# 12V_Converter.net
KiCad netlist of a schematic drawn in Altium Designer
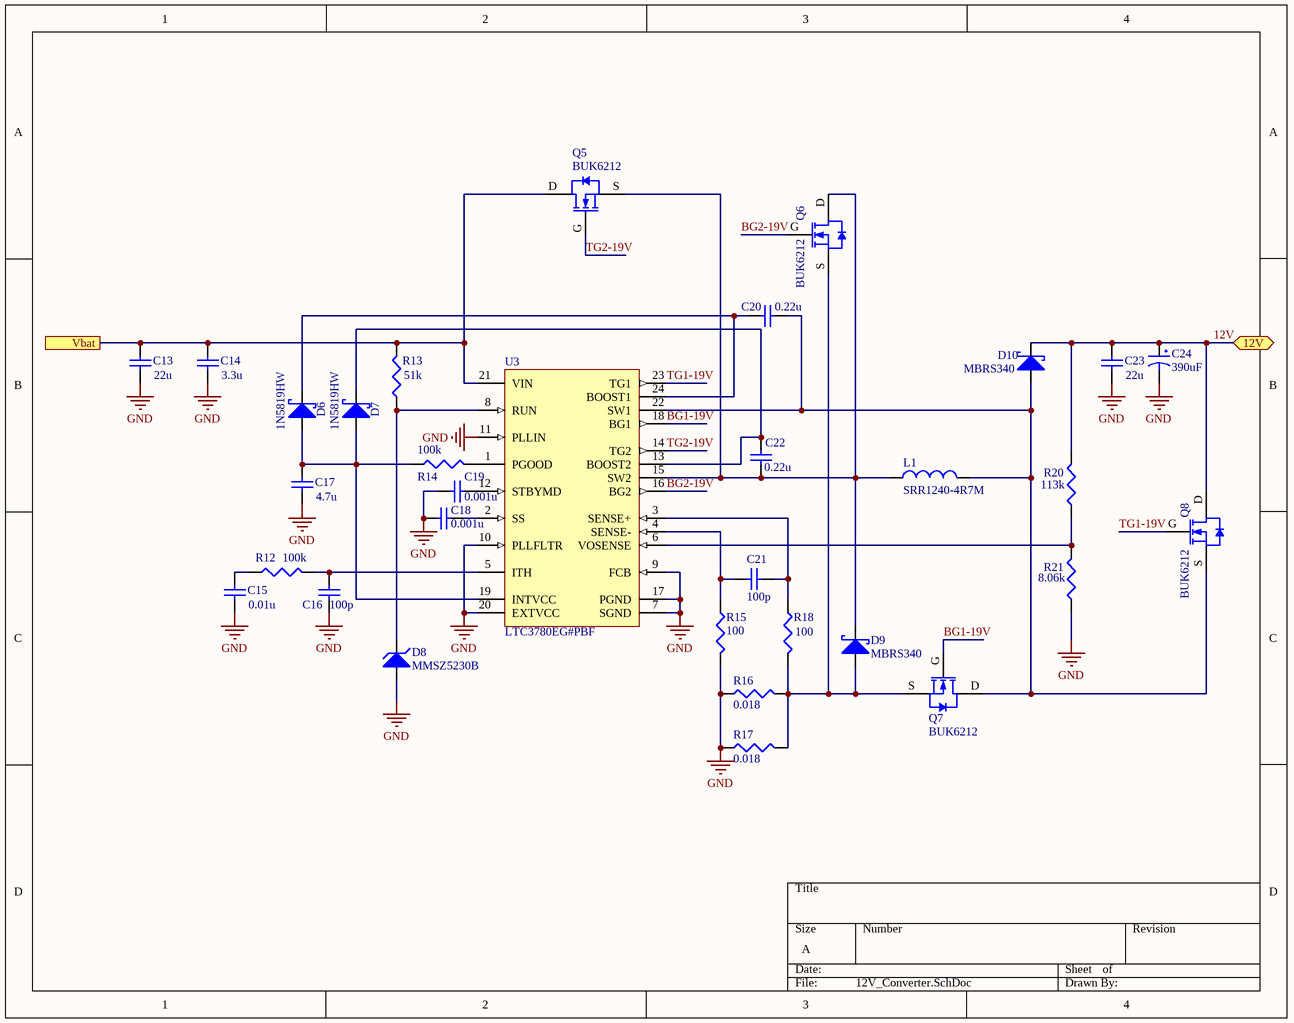
[diagram p0: 12V_Converter.SchDoc]

(export (version "E")
  (design (tool "Eeschema 10.0.6"))
  (components
    (comp (ref "C13")
      (value "22u")
      (footprint "C1206")
      (description "Capacitor (Semiconductor SIM Model)")
      (fields (field (name "Comment") "Cap Semi") (field (name "PUBLISHER") "Altium Limited"))
      (libsource (lib "Miscellaneous Devices") (part "Cap Semi"))
    )
    (comp (ref "C14")
      (value "3.3u")
      (footprint "C1206")
      (description "Capacitor (Semiconductor SIM Model)")
      (fields (field (name "Comment") "Cap Semi") (field (name "PUBLISHER") "Altium Limited"))
      (libsource (lib "Miscellaneous Devices") (part "Cap Semi"))
    )
    (comp (ref "C15")
      (value "0.01u")
      (footprint "C1206")
      (description "Capacitor (Semiconductor SIM Model)")
      (fields (field (name "Comment") "Cap Semi") (field (name "PUBLISHER") "Altium Limited"))
      (libsource (lib "Miscellaneous Devices") (part "Cap Semi"))
    )
    (comp (ref "C16")
      (value "100p")
      (footprint "C1206")
      (description "Capacitor (Semiconductor SIM Model)")
      (fields (field (name "Comment") "Cap Semi") (field (name "PUBLISHER") "Altium Limited"))
      (libsource (lib "Miscellaneous Devices") (part "Cap Semi"))
    )
    (comp (ref "C17")
      (value "4.7u")
      (footprint "C1206")
      (description "Capacitor (Semiconductor SIM Model)")
      (fields (field (name "Comment") "Cap Semi") (field (name "PUBLISHER") "Altium Limited"))
      (libsource (lib "Miscellaneous Devices") (part "Cap Semi"))
    )
    (comp (ref "C18")
      (value "0.001u")
      (footprint "C1206")
      (description "Capacitor (Semiconductor SIM Model)")
      (fields (field (name "Comment") "Cap Semi") (field (name "PUBLISHER") "Altium Limited"))
      (libsource (lib "Miscellaneous Devices") (part "Cap Semi"))
    )
    (comp (ref "C19")
      (value "0.001u")
      (footprint "C1206")
      (description "Capacitor (Semiconductor SIM Model)")
      (fields (field (name "Comment") "Cap Semi") (field (name "PUBLISHER") "Altium Limited"))
      (libsource (lib "Miscellaneous Devices") (part "Cap Semi"))
    )
    (comp (ref "C20")
      (value "0.22u")
      (footprint "C1206")
      (description "Capacitor (Semiconductor SIM Model)")
      (fields (field (name "Comment") "Cap Semi") (field (name "PUBLISHER") "Altium Limited"))
      (libsource (lib "Miscellaneous Devices") (part "Cap Semi"))
    )
    (comp (ref "C21")
      (value "100p")
      (footprint "C1206")
      (description "Capacitor (Semiconductor SIM Model)")
      (fields (field (name "Comment") "Cap Semi") (field (name "PUBLISHER") "Altium Limited"))
      (libsource (lib "Miscellaneous Devices") (part "Cap Semi"))
    )
    (comp (ref "C22")
      (value "0.22u")
      (footprint "C1206")
      (description "Capacitor (Semiconductor SIM Model)")
      (fields (field (name "Comment") "Cap Semi") (field (name "PUBLISHER") "Altium Limited"))
      (libsource (lib "Miscellaneous Devices") (part "Cap Semi"))
    )
    (comp (ref "C23")
      (value "22u")
      (footprint "C1206")
      (description "Capacitor (Semiconductor SIM Model)")
      (fields (field (name "Comment") "Cap Semi") (field (name "PUBLISHER") "Altium Limited"))
      (libsource (lib "Miscellaneous Devices") (part "Cap Semi"))
    )
    (comp (ref "C24")
      (value "390uF")
      (footprint "PCVxxxxxMCLxGS")
      (description "CAP ALUM POLY 390UF 20% 25V SMD")
      (libsource (lib "Power_Embedded_Board_Library") (part "PCV1E391MCL2GS"))
    )
    (comp (ref "D6")
      (value "1N5819HW")
      (footprint "1N58xx")
      (description "1A Schottky Barrier Rectifier Diode")
      (libsource (lib "Power_Embedded_Board_Library") (part "1N58xx"))
    )
    (comp (ref "D7")
      (value "1N5819HW")
      (footprint "1N58xx")
      (description "1A Schottky Barrier Rectifier Diode")
      (libsource (lib "Power_Embedded_Board_Library") (part "1N58xx"))
    )
    (comp (ref "D8")
      (value "MMSZ5230B")
      (footprint "ONSC-SOD-123-2-425-04_V")
      (description "Zener Voltage Regulator, 500 mW, 2-Pin SOD-123, Pb-Free, Tape and Reel")
      (fields (field (name "MANUFACTURER") "On Semiconductor") (field (name "PARTNUMBER") "MMSZ5230BT1G"))
      (libsource (lib "Power_Embedded_Board_Library") (part "MMSZ5230BT1G"))
    )
    (comp (ref "D9")
      (value "MBRS340")
      (footprint "MBRS340")
      (description "Schottky Rectifier")
      (libsource (lib "Power_Embedded_Board_Library") (part "MBRS340"))
    )
    (comp (ref "D10")
      (value "MBRS340")
      (footprint "MBRS340")
      (description "Schottky Rectifier")
      (libsource (lib "Power_Embedded_Board_Library") (part "MBRS340"))
    )
    (comp (ref "L1")
      (value "SRR1240-4R7M")
      (footprint "SRR1240")
      (description "FIXED IND 4.7UH 6A 18 MOHM SMD")
      (libsource (lib "Power_Embedded_Board_Library") (part "SRR1240"))
    )
    (comp (ref "Q5")
      (value "BUK6212")
      (footprint "NXP-SOT428_M")
      (description "N-Channel TrenchMOS Intermediate Level FET, 40 V, 50 A, 3-Pin SOT428, Tape and Reel")
      (fields
        (field (name "MANUFACTURER") "NXP Semiconductors")
        (field (name "PARTNUMBER") "BUK6212-40C,118")
      )
      (libsource (lib "Power_Embedded_Board_Library") (part "BUK6212"))
    )
    (comp (ref "Q6")
      (value "BUK6212")
      (footprint "NXP-SOT428_M")
      (description "N-Channel TrenchMOS Intermediate Level FET, 40 V, 50 A, 3-Pin SOT428, Tape and Reel")
      (fields
        (field (name "MANUFACTURER") "NXP Semiconductors")
        (field (name "PARTNUMBER") "BUK6212-40C,118")
      )
      (libsource (lib "Power_Embedded_Board_Library") (part "BUK6212"))
    )
    (comp (ref "Q7")
      (value "BUK6212")
      (footprint "NXP-SOT428_M")
      (description "N-Channel TrenchMOS Intermediate Level FET, 40 V, 50 A, 3-Pin SOT428, Tape and Reel")
      (fields
        (field (name "MANUFACTURER") "NXP Semiconductors")
        (field (name "PARTNUMBER") "BUK6212-40C,118")
      )
      (libsource (lib "Power_Embedded_Board_Library") (part "BUK6212"))
    )
    (comp (ref "Q8")
      (value "BUK6212")
      (footprint "NXP-SOT428_M")
      (description "N-Channel TrenchMOS Intermediate Level FET, 40 V, 50 A, 3-Pin SOT428, Tape and Reel")
      (fields
        (field (name "MANUFACTURER") "NXP Semiconductors")
        (field (name "PARTNUMBER") "BUK6212-40C,118")
      )
      (libsource (lib "Power_Embedded_Board_Library") (part "BUK6212"))
    )
    (comp (ref "R12")
      (value "100k")
      (footprint "J1-0603")
      (description "Resistor")
      (fields (field (name "Comment") "Res3") (field (name "PUBLISHER") "Altium Limited"))
      (libsource (lib "Miscellaneous Devices") (part "Res3"))
    )
    (comp (ref "R13")
      (value "51k")
      (footprint "J1-0603")
      (description "Resistor")
      (fields (field (name "Comment") "Res3") (field (name "PUBLISHER") "Altium Limited"))
      (libsource (lib "Miscellaneous Devices") (part "Res3"))
    )
    (comp (ref "R14")
      (value "100k")
      (footprint "J1-0603")
      (description "Resistor")
      (fields (field (name "Comment") "Res3") (field (name "PUBLISHER") "Altium Limited"))
      (libsource (lib "Miscellaneous Devices") (part "Res3"))
    )
    (comp (ref "R15")
      (value "100")
      (footprint "J1-0603")
      (description "Resistor")
      (fields (field (name "Comment") "Res3") (field (name "PUBLISHER") "Altium Limited"))
      (libsource (lib "Miscellaneous Devices") (part "Res3"))
    )
    (comp (ref "R16")
      (value "0.018")
      (footprint "R1206")
      (description "Resistor")
      (fields (field (name "Comment") "Res3") (field (name "PUBLISHER") "Altium Limited"))
      (libsource (lib "Miscellaneous Devices") (part "Res3"))
    )
    (comp (ref "R17")
      (value "0.018")
      (footprint "R1206")
      (description "Resistor")
      (fields (field (name "Comment") "Res3") (field (name "PUBLISHER") "Altium Limited"))
      (libsource (lib "Miscellaneous Devices") (part "Res3"))
    )
    (comp (ref "R18")
      (value "100")
      (footprint "J1-0603")
      (description "Resistor")
      (fields (field (name "Comment") "Res3") (field (name "PUBLISHER") "Altium Limited"))
      (libsource (lib "Miscellaneous Devices") (part "Res3"))
    )
    (comp (ref "R20")
      (value "113k")
      (footprint "J1-0603")
      (description "Resistor")
      (fields (field (name "Comment") "Res3") (field (name "PUBLISHER") "Altium Limited"))
      (libsource (lib "Miscellaneous Devices") (part "Res3"))
    )
    (comp (ref "R21")
      (value "8.06k")
      (footprint "J1-0603")
      (description "Resistor")
      (fields (field (name "Comment") "Res3") (field (name "PUBLISHER") "Altium Limited"))
      (libsource (lib "Miscellaneous Devices") (part "Res3"))
    )
    (comp (ref "U3")
      (value "LTC3780EG#PBF")
      (footprint "LT-G-24_L")
      (fields (field (name "MANUFACTURER") "Linear Technology"))
      (libsource (lib "Power_Embedded_Board_Library") (part "LTC3780EG#PBF"))
    )
  )
  (nets
    (net (code "1") (name "/12V") (class "Default")
      (node (ref "C23") (pin "2") (pinfunction "2_2") (pintype "passive"))
      (node (ref "C24") (pin "1") (pinfunction "1_1") (pintype "passive"))
      (node (ref "D10") (pin "K") (pinfunction "Cathode_K") (pintype "passive"))
      (node (ref "Q8") (pin "D") (pinfunction "D_D") (pintype "passive"))
      (node (ref "R20") (pin "2") (pinfunction "2_2") (pintype "passive"))
    )
    (net (code "2") (name "/BG1-19V") (class "Default")
      (node (ref "Q7") (pin "G") (pinfunction "G_G") (pintype "passive"))
      (node (ref "U3") (pin "18") (pinfunction "BG1_18") (pintype "output"))
    )
    (net (code "3") (name "/BG2-19V") (class "Default")
      (node (ref "Q6") (pin "G") (pinfunction "G_G") (pintype "passive"))
      (node (ref "U3") (pin "16") (pinfunction "BG2_16") (pintype "output"))
    )
    (net (code "4") (name "/TG1-19V") (class "Default")
      (node (ref "Q8") (pin "G") (pinfunction "G_G") (pintype "passive"))
      (node (ref "U3") (pin "23") (pinfunction "TG1_23") (pintype "output"))
    )
    (net (code "5") (name "/TG2-19V") (class "Default")
      (node (ref "Q5") (pin "G") (pinfunction "G_G") (pintype "passive"))
      (node (ref "U3") (pin "14") (pinfunction "TG2_14") (pintype "output"))
    )
    (net (code "6") (name "/Vbat") (class "Default")
      (node (ref "C13") (pin "2") (pinfunction "2_2") (pintype "passive"))
      (node (ref "C14") (pin "2") (pinfunction "2_2") (pintype "passive"))
      (node (ref "Q5") (pin "D") (pinfunction "D_D") (pintype "passive"))
      (node (ref "R13") (pin "2") (pinfunction "2_2") (pintype "passive"))
      (node (ref "U3") (pin "21") (pinfunction "VIN_21") (pintype "power_in"))
    )
    (net (code "7") (name "GND") (class "Default")
      (node (ref "C13") (pin "1") (pinfunction "1_1") (pintype "passive"))
      (node (ref "C14") (pin "1") (pinfunction "1_1") (pintype "passive"))
      (node (ref "C15") (pin "1") (pinfunction "1_1") (pintype "passive"))
      (node (ref "C16") (pin "1") (pinfunction "1_1") (pintype "passive"))
      (node (ref "C17") (pin "1") (pinfunction "1_1") (pintype "passive"))
      (node (ref "C18") (pin "1") (pinfunction "1_1") (pintype "passive"))
      (node (ref "C19") (pin "1") (pinfunction "1_1") (pintype "passive"))
      (node (ref "C23") (pin "1") (pinfunction "1_1") (pintype "passive"))
      (node (ref "C24") (pin "2") (pinfunction "2_2") (pintype "passive"))
      (node (ref "D8") (pin "2") (pinfunction "A_2") (pintype "passive"))
      (node (ref "R15") (pin "2") (pinfunction "2_2") (pintype "passive"))
      (node (ref "R16") (pin "1") (pinfunction "1_1") (pintype "passive"))
      (node (ref "R17") (pin "1") (pinfunction "1_1") (pintype "passive"))
      (node (ref "R21") (pin "1") (pinfunction "1_1") (pintype "passive"))
      (node (ref "U3") (pin "10") (pinfunction "PLLFLTR_10") (pintype "input"))
      (node (ref "U3") (pin "11") (pinfunction "PLLIN_11") (pintype "input"))
      (node (ref "U3") (pin "17") (pinfunction "PGND_17") (pintype "power_in"))
      (node (ref "U3") (pin "20") (pinfunction "EXTVCC_20") (pintype "power_in"))
      (node (ref "U3") (pin "7") (pinfunction "SGND_7") (pintype "power_in"))
      (node (ref "U3") (pin "9") (pinfunction "FCB_9") (pintype "input"))
    )
    (net (code "8") (name "Net-(C15-Pad2)") (class "Default")
      (node (ref "C15") (pin "2") (pinfunction "2_2") (pintype "passive"))
      (node (ref "R12") (pin "1") (pinfunction "1_1") (pintype "passive"))
    )
    (net (code "9") (name "Net-(D6-Anode)") (class "Default")
      (node (ref "C17") (pin "2") (pinfunction "2_2") (pintype "passive"))
      (node (ref "D6") (pin "A") (pinfunction "Anode_A") (pintype "passive"))
      (node (ref "D7") (pin "A") (pinfunction "Anode_A") (pintype "passive"))
      (node (ref "R14") (pin "1") (pinfunction "1_1") (pintype "passive"))
      (node (ref "U3") (pin "19") (pinfunction "INTVCC_19") (pintype "power_in"))
    )
    (net (code "10") (name "Net-(D6-Cathode)") (class "Default")
      (node (ref "C20") (pin "2") (pinfunction "2_2") (pintype "passive"))
      (node (ref "D6") (pin "K") (pinfunction "Cathode_K") (pintype "passive"))
      (node (ref "U3") (pin "24") (pinfunction "BOOST1_24") (pintype "passive"))
    )
    (net (code "11") (name "Net-(D7-Cathode)") (class "Default")
      (node (ref "C22") (pin "2") (pinfunction "2_2") (pintype "passive"))
      (node (ref "D7") (pin "K") (pinfunction "Cathode_K") (pintype "passive"))
      (node (ref "U3") (pin "13") (pinfunction "BOOST2_13") (pintype "passive"))
    )
    (net (code "12") (name "Net-(D8-K)") (class "Default")
      (node (ref "D8") (pin "1") (pinfunction "K_1") (pintype "passive"))
      (node (ref "R13") (pin "1") (pinfunction "1_1") (pintype "passive"))
      (node (ref "U3") (pin "8") (pinfunction "RUN_8") (pintype "input"))
    )
    (net (code "13") (name "Net-(D9-Anode)") (class "Default")
      (node (ref "D9") (pin "A") (pinfunction "Anode_A") (pintype "passive"))
      (node (ref "Q6") (pin "S") (pinfunction "S_S") (pintype "passive"))
      (node (ref "Q7") (pin "S") (pinfunction "S_S") (pintype "passive"))
      (node (ref "R16") (pin "2") (pinfunction "2_2") (pintype "passive"))
      (node (ref "R17") (pin "2") (pinfunction "2_2") (pintype "passive"))
      (node (ref "R18") (pin "2") (pinfunction "2_2") (pintype "passive"))
    )
    (net (code "14") (name "Net-(D9-Cathode)") (class "Default")
      (node (ref "C22") (pin "1") (pinfunction "1_1") (pintype "passive"))
      (node (ref "D9") (pin "K") (pinfunction "Cathode_K") (pintype "passive"))
      (node (ref "L1") (pin "1") (pinfunction "1_1") (pintype "passive"))
      (node (ref "Q5") (pin "S") (pinfunction "S_S") (pintype "passive"))
      (node (ref "Q6") (pin "D") (pinfunction "D_D") (pintype "passive"))
      (node (ref "U3") (pin "15") (pinfunction "SW2_15") (pintype "passive"))
    )
    (net (code "15") (name "Net-(D10-Anode)") (class "Default")
      (node (ref "C20") (pin "1") (pinfunction "1_1") (pintype "passive"))
      (node (ref "D10") (pin "A") (pinfunction "Anode_A") (pintype "passive"))
      (node (ref "L1") (pin "2") (pinfunction "2_2") (pintype "passive"))
      (node (ref "Q7") (pin "D") (pinfunction "D_D") (pintype "passive"))
      (node (ref "Q8") (pin "S") (pinfunction "S_S") (pintype "passive"))
      (node (ref "U3") (pin "22") (pinfunction "SW1_22") (pintype "passive"))
    )
    (net (code "16") (name "Net-(U3-ITH)") (class "Default")
      (node (ref "C16") (pin "2") (pinfunction "2_2") (pintype "passive"))
      (node (ref "R12") (pin "2") (pinfunction "2_2") (pintype "passive"))
      (node (ref "U3") (pin "5") (pinfunction "ITH_5") (pintype "passive"))
    )
    (net (code "17") (name "Net-(U3-PGOOD)") (class "Default")
      (node (ref "R14") (pin "2") (pinfunction "2_2") (pintype "passive"))
      (node (ref "U3") (pin "1") (pinfunction "PGOOD_1") (pintype "open_collector"))
    )
    (net (code "18") (name "Net-(U3-SENSE+)") (class "Default")
      (node (ref "C21") (pin "2") (pinfunction "2_2") (pintype "passive"))
      (node (ref "R18") (pin "1") (pinfunction "1_1") (pintype "passive"))
      (node (ref "U3") (pin "3") (pinfunction "SENSE+_3") (pintype "input"))
    )
    (net (code "19") (name "Net-(U3-SENSE-)") (class "Default")
      (node (ref "C21") (pin "1") (pinfunction "1_1") (pintype "passive"))
      (node (ref "R15") (pin "1") (pinfunction "1_1") (pintype "passive"))
      (node (ref "U3") (pin "4") (pinfunction "SENSE-_4") (pintype "input"))
    )
    (net (code "20") (name "Net-(U3-SS)") (class "Default")
      (node (ref "C18") (pin "2") (pinfunction "2_2") (pintype "passive"))
      (node (ref "U3") (pin "2") (pinfunction "SS_2") (pintype "input"))
    )
    (net (code "21") (name "Net-(U3-STBYMD)") (class "Default")
      (node (ref "C19") (pin "2") (pinfunction "2_2") (pintype "passive"))
      (node (ref "U3") (pin "12") (pinfunction "STBYMD_12") (pintype "input"))
    )
    (net (code "22") (name "Net-(U3-VOSENSE)") (class "Default")
      (node (ref "R20") (pin "1") (pinfunction "1_1") (pintype "passive"))
      (node (ref "R21") (pin "2") (pinfunction "2_2") (pintype "passive"))
      (node (ref "U3") (pin "6") (pinfunction "VOSENSE_6") (pintype "input"))
    )
  )
)
